# oscillator-v1.net
KiCad netlist of a schematic drawn in EAGLE
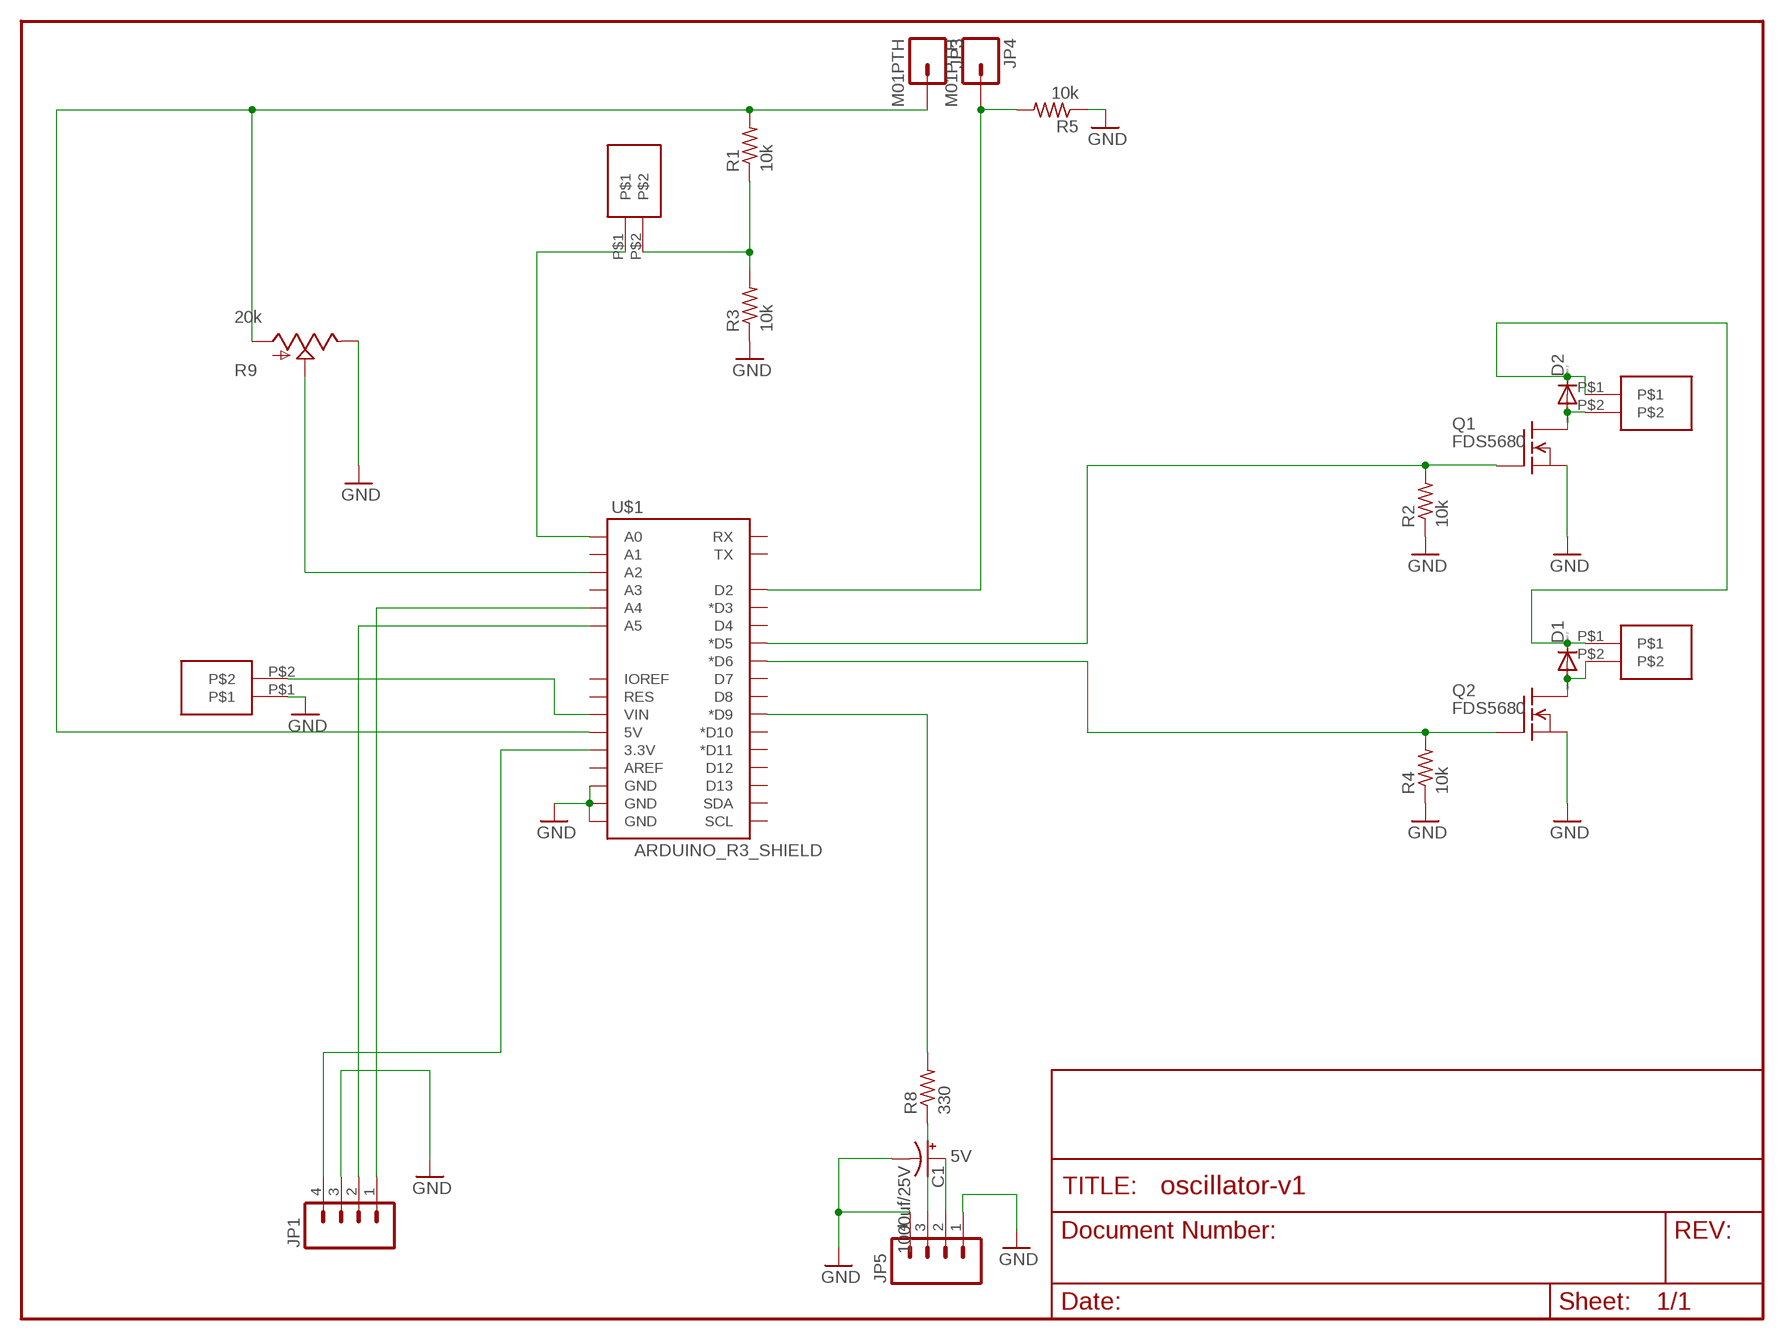
[diagram p0: schematic, sheet 1]

(export (version "E")
  (design (tool "Eeschema 10.0.6"))
  (components
    (comp (ref "C1")
      (value "1000uf/25V")
      (footprint "eagle-import:CPOL-RADIAL-1000UF-25V-KIT")
      (libsource (lib "eagle-import") (part "1000UF-25V(PTH)KIT"))
    )
    (comp (ref "D1")
      (value "DIODE-DO-214AC")
      (footprint "eagle-import:DO-214AC")
      (libsource (lib "eagle-import") (part "DIODE-DO-214AC"))
    )
    (comp (ref "D2")
      (value "DIODE-DO-214AC")
      (footprint "eagle-import:DO-214AC")
      (libsource (lib "eagle-import") (part "DIODE-DO-214AC"))
    )
    (comp (ref "JP1")
      (value "M04PTH")
      (footprint "eagle-import:1X04")
      (libsource (lib "eagle-import") (part "M04PTH"))
    )
    (comp (ref "JP3")
      (value "M01PTH")
      (footprint "eagle-import:1X01")
      (libsource (lib "eagle-import") (part "M01PTH"))
    )
    (comp (ref "JP4")
      (value "M01PTH")
      (footprint "eagle-import:1X01")
      (libsource (lib "eagle-import") (part "M01PTH"))
    )
    (comp (ref "JP5")
      (value "M04PTH")
      (footprint "eagle-import:1X04")
      (libsource (lib "eagle-import") (part "M04PTH"))
    )
    (comp (ref "Q1")
      (value "FDS5680")
      (footprint "eagle-import:SO-8")
      (libsource (lib "eagle-import") (part "FDS5680"))
    )
    (comp (ref "Q2")
      (value "FDS5680")
      (footprint "eagle-import:SO-8")
      (libsource (lib "eagle-import") (part "FDS5680"))
    )
    (comp (ref "R1")
      (value "10k")
      (footprint "eagle-import:R0603")
      (libsource (lib "eagle-import") (part "R-US_R0603"))
    )
    (comp (ref "R2")
      (value "10k")
      (footprint "eagle-import:R0603")
      (libsource (lib "eagle-import") (part "R-US_R0603"))
    )
    (comp (ref "R3")
      (value "10k")
      (footprint "eagle-import:R0603")
      (libsource (lib "eagle-import") (part "R-US_R0603"))
    )
    (comp (ref "R4")
      (value "10k")
      (footprint "eagle-import:R0603")
      (libsource (lib "eagle-import") (part "R-US_R0603"))
    )
    (comp (ref "R5")
      (value "10k")
      (footprint "eagle-import:R0603")
      (libsource (lib "eagle-import") (part "R-US_R0603"))
    )
    (comp (ref "R8")
      (value "330")
      (footprint "eagle-import:R0603")
      (libsource (lib "eagle-import") (part "R-US_R0603"))
    )
    (comp (ref "R9")
      (value "20k")
      (footprint "eagle-import:ALPS_POT_KIT")
      (libsource (lib "eagle-import") (part "POTALPS-KIT"))
    )
    (comp (ref "U$1")
      (value "ARDUINO_R3_SHIELD")
      (footprint "eagle-import:UNO_R3_SHIELD")
      (libsource (lib "eagle-import") (part "ARDUINO_R3_SHIELD"))
    )
    (comp (ref "U$6")
      (value "SPRING-TERMINAL")
      (footprint "eagle-import:SPRING-TERMINAL")
      (libsource (lib "eagle-import") (part "SPRING-TERMINAL"))
    )
    (comp (ref "X1")
      (value "SPRING-TERMINAL")
      (footprint "eagle-import:SPRING-TERMINAL")
      (libsource (lib "eagle-import") (part "SPRING-TERMINAL"))
    )
    (comp (ref "X2")
      (value "SPRING-TERMINAL")
      (footprint "eagle-import:SPRING-TERMINAL")
      (libsource (lib "eagle-import") (part "SPRING-TERMINAL"))
    )
    (comp (ref "X5")
      (value "SPRING-TERMINAL")
      (footprint "eagle-import:SPRING-TERMINAL")
      (libsource (lib "eagle-import") (part "SPRING-TERMINAL"))
    )
  )
  (nets
    (net (code "1") (name "/5V") (class "Default")
      (node (ref "C1") (pin "+") (pinfunction "+_+") (pintype "passive"))
      (node (ref "JP3") (pin "1") (pinfunction "1_1") (pintype "passive"))
      (node (ref "JP5") (pin "2") (pinfunction "2_2") (pintype "passive"))
      (node (ref "R1") (pin "2") (pinfunction "2_2") (pintype "passive"))
      (node (ref "R9") (pin "P$3") (pinfunction "A_P$3") (pintype "passive"))
      (node (ref "U$1") (pin "5V") (pinfunction "5V_5V") (pintype "bidirectional"))
    )
    (net (code "2") (name "/VIN") (class "Default")
      (node (ref "D1") (pin "C") (pinfunction "C_C") (pintype "passive"))
      (node (ref "D2") (pin "C") (pinfunction "C_C") (pintype "passive"))
      (node (ref "U$1") (pin "VIN") (pinfunction "VIN_VIN") (pintype "bidirectional"))
      (node (ref "U$6") (pin "P$1") (pinfunction "P$1_P$1") (pintype "bidirectional"))
      (node (ref "X1") (pin "P$2") (pinfunction "P$2_P$2") (pintype "bidirectional"))
      (node (ref "X5") (pin "P$1") (pinfunction "P$1_P$1") (pintype "bidirectional"))
    )
    (net (code "3") (name "GND") (class "Default")
      (node (ref "C1") (pin "-") (pinfunction "-_-") (pintype "passive"))
      (node (ref "JP1") (pin "3") (pinfunction "3_3") (pintype "passive"))
      (node (ref "JP5") (pin "1") (pinfunction "1_1") (pintype "passive"))
      (node (ref "JP5") (pin "4") (pinfunction "4_4") (pintype "passive"))
      (node (ref "Q1") (pin "1") (pinfunction "S_1") (pintype "passive"))
      (node (ref "Q1") (pin "2") (pinfunction "S_2") (pintype "passive"))
      (node (ref "Q1") (pin "3") (pinfunction "S_3") (pintype "passive"))
      (node (ref "Q2") (pin "1") (pinfunction "S_1") (pintype "passive"))
      (node (ref "Q2") (pin "2") (pinfunction "S_2") (pintype "passive"))
      (node (ref "Q2") (pin "3") (pinfunction "S_3") (pintype "passive"))
      (node (ref "R2") (pin "1") (pinfunction "1_1") (pintype "passive"))
      (node (ref "R3") (pin "1") (pinfunction "1_1") (pintype "passive"))
      (node (ref "R4") (pin "1") (pinfunction "1_1") (pintype "passive"))
      (node (ref "R5") (pin "1") (pinfunction "1_1") (pintype "passive"))
      (node (ref "R9") (pin "P$1") (pinfunction "E_P$1") (pintype "passive"))
      (node (ref "U$1") (pin "GND@0") (pinfunction "GND_GND@0") (pintype "bidirectional"))
      (node (ref "U$1") (pin "GND@1") (pinfunction "GND_GND@1") (pintype "bidirectional"))
      (node (ref "U$1") (pin "GND@2") (pinfunction "GND_GND@2") (pintype "bidirectional"))
      (node (ref "X1") (pin "P$1") (pinfunction "P$1_P$1") (pintype "bidirectional"))
    )
    (net (code "4") (name "Net-(D1-PadA)") (class "Default")
      (node (ref "D1") (pin "A") (pinfunction "A_A") (pintype "passive"))
      (node (ref "Q2") (pin "5") (pinfunction "D_5") (pintype "passive"))
      (node (ref "Q2") (pin "6") (pinfunction "D_6") (pintype "passive"))
      (node (ref "Q2") (pin "7") (pinfunction "D_7") (pintype "passive"))
      (node (ref "Q2") (pin "8") (pinfunction "D_8") (pintype "passive"))
      (node (ref "X5") (pin "P$2") (pinfunction "P$2_P$2") (pintype "bidirectional"))
    )
    (net (code "5") (name "Net-(D2-PadA)") (class "Default")
      (node (ref "D2") (pin "A") (pinfunction "A_A") (pintype "passive"))
      (node (ref "Q1") (pin "5") (pinfunction "D_5") (pintype "passive"))
      (node (ref "Q1") (pin "6") (pinfunction "D_6") (pintype "passive"))
      (node (ref "Q1") (pin "7") (pinfunction "D_7") (pintype "passive"))
      (node (ref "Q1") (pin "8") (pinfunction "D_8") (pintype "passive"))
      (node (ref "U$6") (pin "P$2") (pinfunction "P$2_P$2") (pintype "bidirectional"))
    )
    (net (code "6") (name "Net-(JP1-Pad1)") (class "Default")
      (node (ref "JP1") (pin "1") (pinfunction "1_1") (pintype "passive"))
      (node (ref "U$1") (pin "A4") (pinfunction "A4_A4") (pintype "bidirectional"))
    )
    (net (code "7") (name "Net-(JP1-Pad2)") (class "Default")
      (node (ref "JP1") (pin "2") (pinfunction "2_2") (pintype "passive"))
      (node (ref "U$1") (pin "A5") (pinfunction "A5_A5") (pintype "bidirectional"))
    )
    (net (code "8") (name "Net-(JP1-Pad4)") (class "Default")
      (node (ref "JP1") (pin "4") (pinfunction "4_4") (pintype "passive"))
      (node (ref "U$1") (pin "3.3V") (pinfunction "3.3V_3.3V") (pintype "bidirectional"))
    )
    (net (code "9") (name "Net-(JP4-Pad1)") (class "Default")
      (node (ref "JP4") (pin "1") (pinfunction "1_1") (pintype "passive"))
      (node (ref "R5") (pin "2") (pinfunction "2_2") (pintype "passive"))
      (node (ref "U$1") (pin "D2") (pinfunction "D2_D2") (pintype "bidirectional"))
    )
    (net (code "10") (name "Net-(JP5-Pad3)") (class "Default")
      (node (ref "JP5") (pin "3") (pinfunction "3_3") (pintype "passive"))
      (node (ref "R8") (pin "1") (pinfunction "1_1") (pintype "passive"))
    )
    (net (code "11") (name "Net-(Q1-G)") (class "Default")
      (node (ref "Q1") (pin "4") (pinfunction "G_4") (pintype "passive"))
      (node (ref "R2") (pin "2") (pinfunction "2_2") (pintype "passive"))
      (node (ref "U$1") (pin "D5") (pinfunction "*D5_D5") (pintype "bidirectional"))
    )
    (net (code "12") (name "Net-(Q2-G)") (class "Default")
      (node (ref "Q2") (pin "4") (pinfunction "G_4") (pintype "passive"))
      (node (ref "R4") (pin "2") (pinfunction "2_2") (pintype "passive"))
      (node (ref "U$1") (pin "D6") (pinfunction "*D6_D6") (pintype "bidirectional"))
    )
    (net (code "13") (name "Net-(R1-Pad1)") (class "Default")
      (node (ref "R1") (pin "1") (pinfunction "1_1") (pintype "passive"))
      (node (ref "R3") (pin "2") (pinfunction "2_2") (pintype "passive"))
      (node (ref "X2") (pin "P$2") (pinfunction "P$2_P$2") (pintype "bidirectional"))
    )
    (net (code "14") (name "Net-(R9-S)") (class "Default")
      (node (ref "R9") (pin "P$2") (pinfunction "S_P$2") (pintype "passive"))
      (node (ref "U$1") (pin "A2") (pinfunction "A2_A2") (pintype "bidirectional"))
    )
    (net (code "15") (name "Net-(U$1-*D9)") (class "Default")
      (node (ref "R8") (pin "2") (pinfunction "2_2") (pintype "passive"))
      (node (ref "U$1") (pin "D9") (pinfunction "*D9_D9") (pintype "bidirectional"))
    )
    (net (code "16") (name "Net-(U$1-PadA0)") (class "Default")
      (node (ref "U$1") (pin "A0") (pinfunction "A0_A0") (pintype "bidirectional"))
      (node (ref "X2") (pin "P$1") (pinfunction "P$1_P$1") (pintype "bidirectional"))
    )
    (net (code "17") (name "unconnected-(U$1-*D3-PadD3)") (class "Default")
      (node (ref "U$1") (pin "D3") (pinfunction "*D3_D3") (pintype "bidirectional"))
    )
    (net (code "18") (name "unconnected-(U$1-*D10-PadD10)") (class "Default")
      (node (ref "U$1") (pin "D10") (pinfunction "*D10_D10") (pintype "bidirectional"))
    )
    (net (code "19") (name "unconnected-(U$1-*D11-PadD11)") (class "Default")
      (node (ref "U$1") (pin "D11") (pinfunction "*D11_D11") (pintype "bidirectional"))
    )
    (net (code "20") (name "unconnected-(U$1-PadA1)") (class "Default")
      (node (ref "U$1") (pin "A1") (pinfunction "A1_A1") (pintype "bidirectional"))
    )
    (net (code "21") (name "unconnected-(U$1-PadA3)") (class "Default")
      (node (ref "U$1") (pin "A3") (pinfunction "A3_A3") (pintype "bidirectional"))
    )
    (net (code "22") (name "unconnected-(U$1-PadAREF)") (class "Default")
      (node (ref "U$1") (pin "AREF") (pinfunction "AREF_AREF") (pintype "bidirectional"))
    )
    (net (code "23") (name "unconnected-(U$1-PadD4)") (class "Default")
      (node (ref "U$1") (pin "D4") (pinfunction "D4_D4") (pintype "bidirectional"))
    )
    (net (code "24") (name "unconnected-(U$1-PadD7)") (class "Default")
      (node (ref "U$1") (pin "D7") (pinfunction "D7_D7") (pintype "bidirectional"))
    )
    (net (code "25") (name "unconnected-(U$1-PadD8)") (class "Default")
      (node (ref "U$1") (pin "D8") (pinfunction "D8_D8") (pintype "bidirectional"))
    )
    (net (code "26") (name "unconnected-(U$1-PadD12)") (class "Default")
      (node (ref "U$1") (pin "D12") (pinfunction "D12_D12") (pintype "bidirectional"))
    )
    (net (code "27") (name "unconnected-(U$1-PadD13)") (class "Default")
      (node (ref "U$1") (pin "D13") (pinfunction "D13_D13") (pintype "bidirectional"))
    )
    (net (code "28") (name "unconnected-(U$1-PadIOREF)") (class "Default")
      (node (ref "U$1") (pin "IOREF") (pinfunction "IOREF_IOREF") (pintype "bidirectional"))
    )
    (net (code "29") (name "unconnected-(U$1-PadRES)") (class "Default")
      (node (ref "U$1") (pin "RES") (pinfunction "RES_RES") (pintype "bidirectional"))
    )
    (net (code "30") (name "unconnected-(U$1-PadRX)") (class "Default")
      (node (ref "U$1") (pin "RX") (pinfunction "RX_RX") (pintype "bidirectional"))
    )
    (net (code "31") (name "unconnected-(U$1-PadSCL)") (class "Default")
      (node (ref "U$1") (pin "SCL") (pinfunction "SCL_SCL") (pintype "bidirectional"))
    )
    (net (code "32") (name "unconnected-(U$1-PadSDA)") (class "Default")
      (node (ref "U$1") (pin "SDA") (pinfunction "SDA_SDA") (pintype "bidirectional"))
    )
    (net (code "33") (name "unconnected-(U$1-PadTX)") (class "Default")
      (node (ref "U$1") (pin "TX") (pinfunction "TX_TX") (pintype "bidirectional"))
    )
  )
)
